# transistor-test.net
KiCad netlist of a schematic drawn in EAGLE
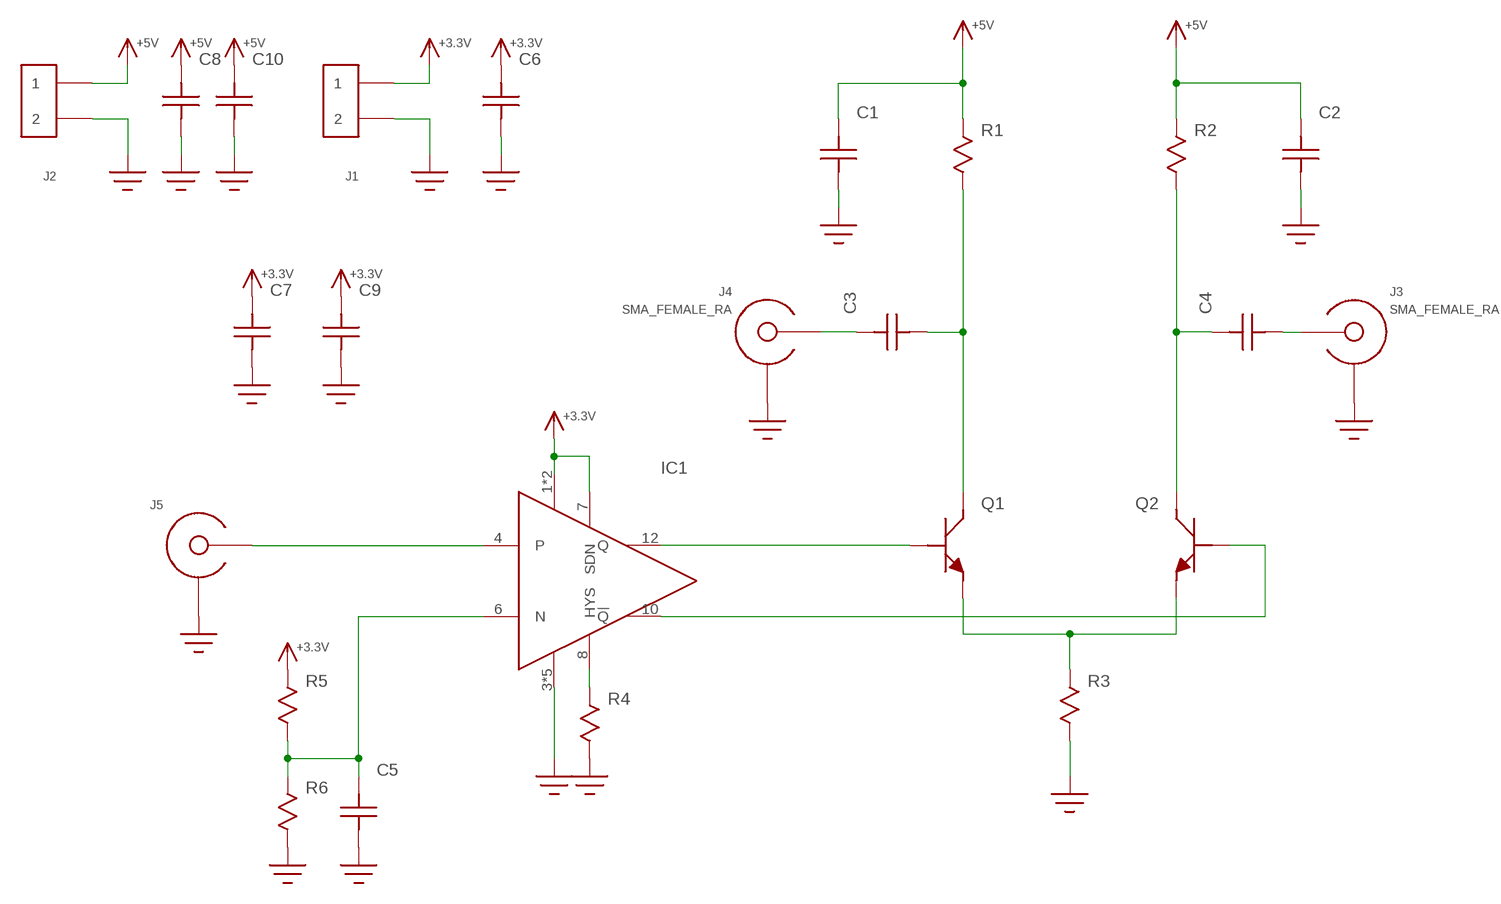
[diagram p0: schematic, sheet 1]

(export (version "E")
  (design (tool "Eeschema 10.0.6"))
  (components
    (comp (ref "C1")
      (value "C0603")
      (footprint "eagle-import:C0603")
      (libsource (lib "eagle-import") (part "C0603"))
    )
    (comp (ref "C2")
      (value "C0603")
      (footprint "eagle-import:C0603")
      (libsource (lib "eagle-import") (part "C0603"))
    )
    (comp (ref "C3")
      (value "C0603")
      (footprint "eagle-import:C0603")
      (libsource (lib "eagle-import") (part "C0603"))
    )
    (comp (ref "C4")
      (value "C0603")
      (footprint "eagle-import:C0603")
      (libsource (lib "eagle-import") (part "C0603"))
    )
    (comp (ref "C5")
      (value "C0603")
      (footprint "eagle-import:C0603")
      (libsource (lib "eagle-import") (part "C0603"))
    )
    (comp (ref "C6")
      (value "C1206")
      (footprint "eagle-import:1206")
      (libsource (lib "eagle-import") (part "C1206"))
    )
    (comp (ref "C7")
      (value "C0603")
      (footprint "eagle-import:C0603")
      (libsource (lib "eagle-import") (part "C0603"))
    )
    (comp (ref "C8")
      (value "C1206")
      (footprint "eagle-import:1206")
      (libsource (lib "eagle-import") (part "C1206"))
    )
    (comp (ref "C9")
      (value "C0603")
      (footprint "eagle-import:C0603")
      (libsource (lib "eagle-import") (part "C0603"))
    )
    (comp (ref "C10")
      (value "C1206")
      (footprint "eagle-import:1206")
      (libsource (lib "eagle-import") (part "C1206"))
    )
    (comp (ref "IC1")
      (value "ADCMP607")
      (footprint "eagle-import:QFN12-3X3")
      (libsource (lib "eagle-import") (part "ADCMP607"))
    )
    (comp (ref "J1")
      (value "HEADER_2PIN")
      (footprint "eagle-import:HEADER_2PIN")
      (libsource (lib "eagle-import") (part "HEADER_2PIN"))
    )
    (comp (ref "J2")
      (value "HEADER_2PIN")
      (footprint "eagle-import:HEADER_2PIN")
      (libsource (lib "eagle-import") (part "HEADER_2PIN"))
    )
    (comp (ref "J3")
      (value "SMA_FEMALE_RA")
      (footprint "eagle-import:SMA_RA_PCB")
      (libsource (lib "eagle-import") (part "SMA_FEMALE_RA"))
    )
    (comp (ref "J4")
      (value "SMA_FEMALE_RA")
      (footprint "eagle-import:SMA_RA_PCB")
      (libsource (lib "eagle-import") (part "SMA_FEMALE_RA"))
    )
    (comp (ref "J5")
      (value "SMA_END_LAUNCH2L")
      (footprint "eagle-import:SMA_EDGE_LAUNCH_2L")
      (libsource (lib "eagle-import") (part "SMA_END_LAUNCH2L"))
    )
    (comp (ref "Q1")
      (value "MMBTH10")
      (footprint "eagle-import:SOT-23")
      (libsource (lib "eagle-import") (part "MMBTH10"))
    )
    (comp (ref "Q2")
      (value "MMBTH10")
      (footprint "eagle-import:SOT-23")
      (libsource (lib "eagle-import") (part "MMBTH10"))
    )
    (comp (ref "R1")
      (value "R0603")
      (footprint "eagle-import:R0603")
      (libsource (lib "eagle-import") (part "R0603"))
    )
    (comp (ref "R2")
      (value "R0603")
      (footprint "eagle-import:R0603")
      (libsource (lib "eagle-import") (part "R0603"))
    )
    (comp (ref "R3")
      (value "R0603")
      (footprint "eagle-import:R0603")
      (libsource (lib "eagle-import") (part "R0603"))
    )
    (comp (ref "R4")
      (value "R0603")
      (footprint "eagle-import:R0603")
      (libsource (lib "eagle-import") (part "R0603"))
    )
    (comp (ref "R5")
      (value "R0603")
      (footprint "eagle-import:R0603")
      (libsource (lib "eagle-import") (part "R0603"))
    )
    (comp (ref "R6")
      (value "R0603")
      (footprint "eagle-import:R0603")
      (libsource (lib "eagle-import") (part "R0603"))
    )
  )
  (nets
    (net (code "1") (name "+3.3V") (class "Default")
      (node (ref "C6") (pin "P$2") (pinfunction "P$2_P$2") (pintype "bidirectional"))
      (node (ref "C7") (pin "P$2") (pinfunction "P$2_P$2") (pintype "bidirectional"))
      (node (ref "C9") (pin "P$2") (pinfunction "P$2_P$2") (pintype "bidirectional"))
      (node (ref "IC1") (pin "1") (pinfunction "VCC_1") (pintype "bidirectional"))
      (node (ref "IC1") (pin "2") (pinfunction "VCC_2") (pintype "bidirectional"))
      (node (ref "IC1") (pin "7") (pinfunction "SDN_7") (pintype "bidirectional"))
      (node (ref "J1") (pin "1") (pinfunction "1_1") (pintype "bidirectional"))
      (node (ref "R5") (pin "P$1") (pinfunction "P$3_P$1") (pintype "bidirectional"))
    )
    (net (code "2") (name "+5V") (class "Default")
      (node (ref "C1") (pin "P$2") (pinfunction "P$2_P$2") (pintype "bidirectional"))
      (node (ref "C10") (pin "P$2") (pinfunction "P$2_P$2") (pintype "bidirectional"))
      (node (ref "C2") (pin "P$2") (pinfunction "P$2_P$2") (pintype "bidirectional"))
      (node (ref "C8") (pin "P$2") (pinfunction "P$2_P$2") (pintype "bidirectional"))
      (node (ref "J2") (pin "1") (pinfunction "1_1") (pintype "bidirectional"))
      (node (ref "R1") (pin "P$1") (pinfunction "P$3_P$1") (pintype "bidirectional"))
      (node (ref "R2") (pin "P$1") (pinfunction "P$3_P$1") (pintype "bidirectional"))
    )
    (net (code "3") (name "GND") (class "Default")
      (node (ref "C1") (pin "P$1") (pinfunction "P$1_P$1") (pintype "bidirectional"))
      (node (ref "C10") (pin "P$1") (pinfunction "P$1_P$1") (pintype "bidirectional"))
      (node (ref "C2") (pin "P$1") (pinfunction "P$1_P$1") (pintype "bidirectional"))
      (node (ref "C5") (pin "P$1") (pinfunction "P$1_P$1") (pintype "bidirectional"))
      (node (ref "C6") (pin "P$1") (pinfunction "P$1_P$1") (pintype "bidirectional"))
      (node (ref "C7") (pin "P$1") (pinfunction "P$1_P$1") (pintype "bidirectional"))
      (node (ref "C8") (pin "P$1") (pinfunction "P$1_P$1") (pintype "bidirectional"))
      (node (ref "C9") (pin "P$1") (pinfunction "P$1_P$1") (pintype "bidirectional"))
      (node (ref "IC1") (pin "11") (pinfunction "VEE_11") (pintype "bidirectional"))
      (node (ref "IC1") (pin "3") (pinfunction "VEE_3") (pintype "bidirectional"))
      (node (ref "IC1") (pin "5") (pinfunction "VEE_5") (pintype "bidirectional"))
      (node (ref "IC1") (pin "9") (pinfunction "VEE_9") (pintype "bidirectional"))
      (node (ref "IC1") (pin "EP") (pinfunction "VEE_EP") (pintype "bidirectional"))
      (node (ref "J1") (pin "2") (pinfunction "2_2") (pintype "bidirectional"))
      (node (ref "J2") (pin "2") (pinfunction "2_2") (pintype "bidirectional"))
      (node (ref "J3") (pin "SHIELD@1") (pinfunction "SHIELD_SHIELD@1") (pintype "bidirectional"))
      (node (ref "J3") (pin "SHIELD@2") (pinfunction "SHIELD_SHIELD@2") (pintype "bidirectional"))
      (node (ref "J3") (pin "SHIELD@3") (pinfunction "SHIELD_SHIELD@3") (pintype "bidirectional"))
      (node (ref "J3") (pin "SHIELD@4") (pinfunction "SHIELD_SHIELD@4") (pintype "bidirectional"))
      (node (ref "J4") (pin "SHIELD@1") (pinfunction "SHIELD_SHIELD@1") (pintype "bidirectional"))
      (node (ref "J4") (pin "SHIELD@2") (pinfunction "SHIELD_SHIELD@2") (pintype "bidirectional"))
      (node (ref "J4") (pin "SHIELD@3") (pinfunction "SHIELD_SHIELD@3") (pintype "bidirectional"))
      (node (ref "J4") (pin "SHIELD@4") (pinfunction "SHIELD_SHIELD@4") (pintype "bidirectional"))
      (node (ref "J5") (pin "BOTTOM_GND") (pinfunction "SHIELD_BOTTOM_GND") (pintype "bidirectional"))
      (node (ref "J5") (pin "GND@1") (pinfunction "SHIELD_GND@1") (pintype "bidirectional"))
      (node (ref "J5") (pin "GND@11") (pinfunction "SHIELD_GND@11") (pintype "bidirectional"))
      (node (ref "J5") (pin "GND@12") (pinfunction "SHIELD_GND@12") (pintype "bidirectional"))
      (node (ref "J5") (pin "GND@14") (pinfunction "SHIELD_GND@14") (pintype "bidirectional"))
      (node (ref "J5") (pin "GND@15") (pinfunction "SHIELD_GND@15") (pintype "bidirectional"))
      (node (ref "J5") (pin "GND@16") (pinfunction "SHIELD_GND@16") (pintype "bidirectional"))
      (node (ref "J5") (pin "GND@17") (pinfunction "SHIELD_GND@17") (pintype "bidirectional"))
      (node (ref "J5") (pin "GND@2") (pinfunction "SHIELD_GND@2") (pintype "bidirectional"))
      (node (ref "J5") (pin "GND@3") (pinfunction "SHIELD_GND@3") (pintype "bidirectional"))
      (node (ref "J5") (pin "GND@4") (pinfunction "SHIELD_GND@4") (pintype "bidirectional"))
      (node (ref "J5") (pin "GND@5") (pinfunction "SHIELD_GND@5") (pintype "bidirectional"))
      (node (ref "J5") (pin "GND@6") (pinfunction "SHIELD_GND@6") (pintype "bidirectional"))
      (node (ref "J5") (pin "GND@7") (pinfunction "SHIELD_GND@7") (pintype "bidirectional"))
      (node (ref "J5") (pin "GND@8") (pinfunction "SHIELD_GND@8") (pintype "bidirectional"))
      (node (ref "J5") (pin "GND_PAD1") (pinfunction "SHIELD_GND_PAD1") (pintype "bidirectional"))
      (node (ref "J5") (pin "GND_PAD2") (pinfunction "SHIELD_GND_PAD2") (pintype "bidirectional"))
      (node (ref "R3") (pin "P$2") (pinfunction "P$4_P$2") (pintype "bidirectional"))
      (node (ref "R4") (pin "P$2") (pinfunction "P$4_P$2") (pintype "bidirectional"))
      (node (ref "R6") (pin "P$2") (pinfunction "P$4_P$2") (pintype "bidirectional"))
    )
    (net (code "4") (name "Net-(C3-PadP$2)") (class "Default")
      (node (ref "C3") (pin "P$2") (pinfunction "P$2_P$2") (pintype "bidirectional"))
      (node (ref "J4") (pin "CENTER") (pinfunction "CENTER_CENTER") (pintype "bidirectional"))
    )
    (net (code "5") (name "Net-(C4-PadP$1)") (class "Default")
      (node (ref "C4") (pin "P$1") (pinfunction "P$1_P$1") (pintype "bidirectional"))
      (node (ref "J3") (pin "CENTER") (pinfunction "CENTER_CENTER") (pintype "bidirectional"))
    )
    (net (code "6") (name "Net-(IC1-HYS)") (class "Default")
      (node (ref "IC1") (pin "8") (pinfunction "HYS_8") (pintype "bidirectional"))
      (node (ref "R4") (pin "P$1") (pinfunction "P$3_P$1") (pintype "bidirectional"))
    )
    (net (code "7") (name "Net-(IC1-N)") (class "Default")
      (node (ref "C5") (pin "P$2") (pinfunction "P$2_P$2") (pintype "bidirectional"))
      (node (ref "IC1") (pin "6") (pinfunction "N_6") (pintype "bidirectional"))
      (node (ref "R5") (pin "P$2") (pinfunction "P$4_P$2") (pintype "bidirectional"))
      (node (ref "R6") (pin "P$1") (pinfunction "P$3_P$1") (pintype "bidirectional"))
    )
    (net (code "8") (name "Net-(IC1-P)") (class "Default")
      (node (ref "IC1") (pin "4") (pinfunction "P_4") (pintype "bidirectional"))
      (node (ref "J5") (pin "CENTER@1") (pinfunction "CENTER_CENTER@1") (pintype "bidirectional"))
    )
    (net (code "9") (name "Net-(IC1-Q)") (class "Default")
      (node (ref "IC1") (pin "12") (pinfunction "Q_12") (pintype "bidirectional"))
      (node (ref "Q1") (pin "1") (pinfunction "B_1") (pintype "bidirectional"))
    )
    (net (code "10") (name "Net-(IC1-~{Q})") (class "Default")
      (node (ref "IC1") (pin "10") (pinfunction "~{Q}_10") (pintype "bidirectional"))
      (node (ref "Q2") (pin "1") (pinfunction "B_1") (pintype "bidirectional"))
    )
    (net (code "11") (name "Net-(Q1-C)") (class "Default")
      (node (ref "C3") (pin "P$1") (pinfunction "P$1_P$1") (pintype "bidirectional"))
      (node (ref "Q1") (pin "3") (pinfunction "C_3") (pintype "bidirectional"))
      (node (ref "R1") (pin "P$2") (pinfunction "P$4_P$2") (pintype "bidirectional"))
    )
    (net (code "12") (name "Net-(Q1-E)") (class "Default")
      (node (ref "Q1") (pin "2") (pinfunction "E_2") (pintype "bidirectional"))
      (node (ref "Q2") (pin "2") (pinfunction "E_2") (pintype "bidirectional"))
      (node (ref "R3") (pin "P$1") (pinfunction "P$3_P$1") (pintype "bidirectional"))
    )
    (net (code "13") (name "Net-(Q2-C)") (class "Default")
      (node (ref "C4") (pin "P$2") (pinfunction "P$2_P$2") (pintype "bidirectional"))
      (node (ref "Q2") (pin "3") (pinfunction "C_3") (pintype "bidirectional"))
      (node (ref "R2") (pin "P$2") (pinfunction "P$4_P$2") (pintype "bidirectional"))
    )
  )
)
